# snowflake.net
KiCad netlist of a schematic drawn in EAGLE
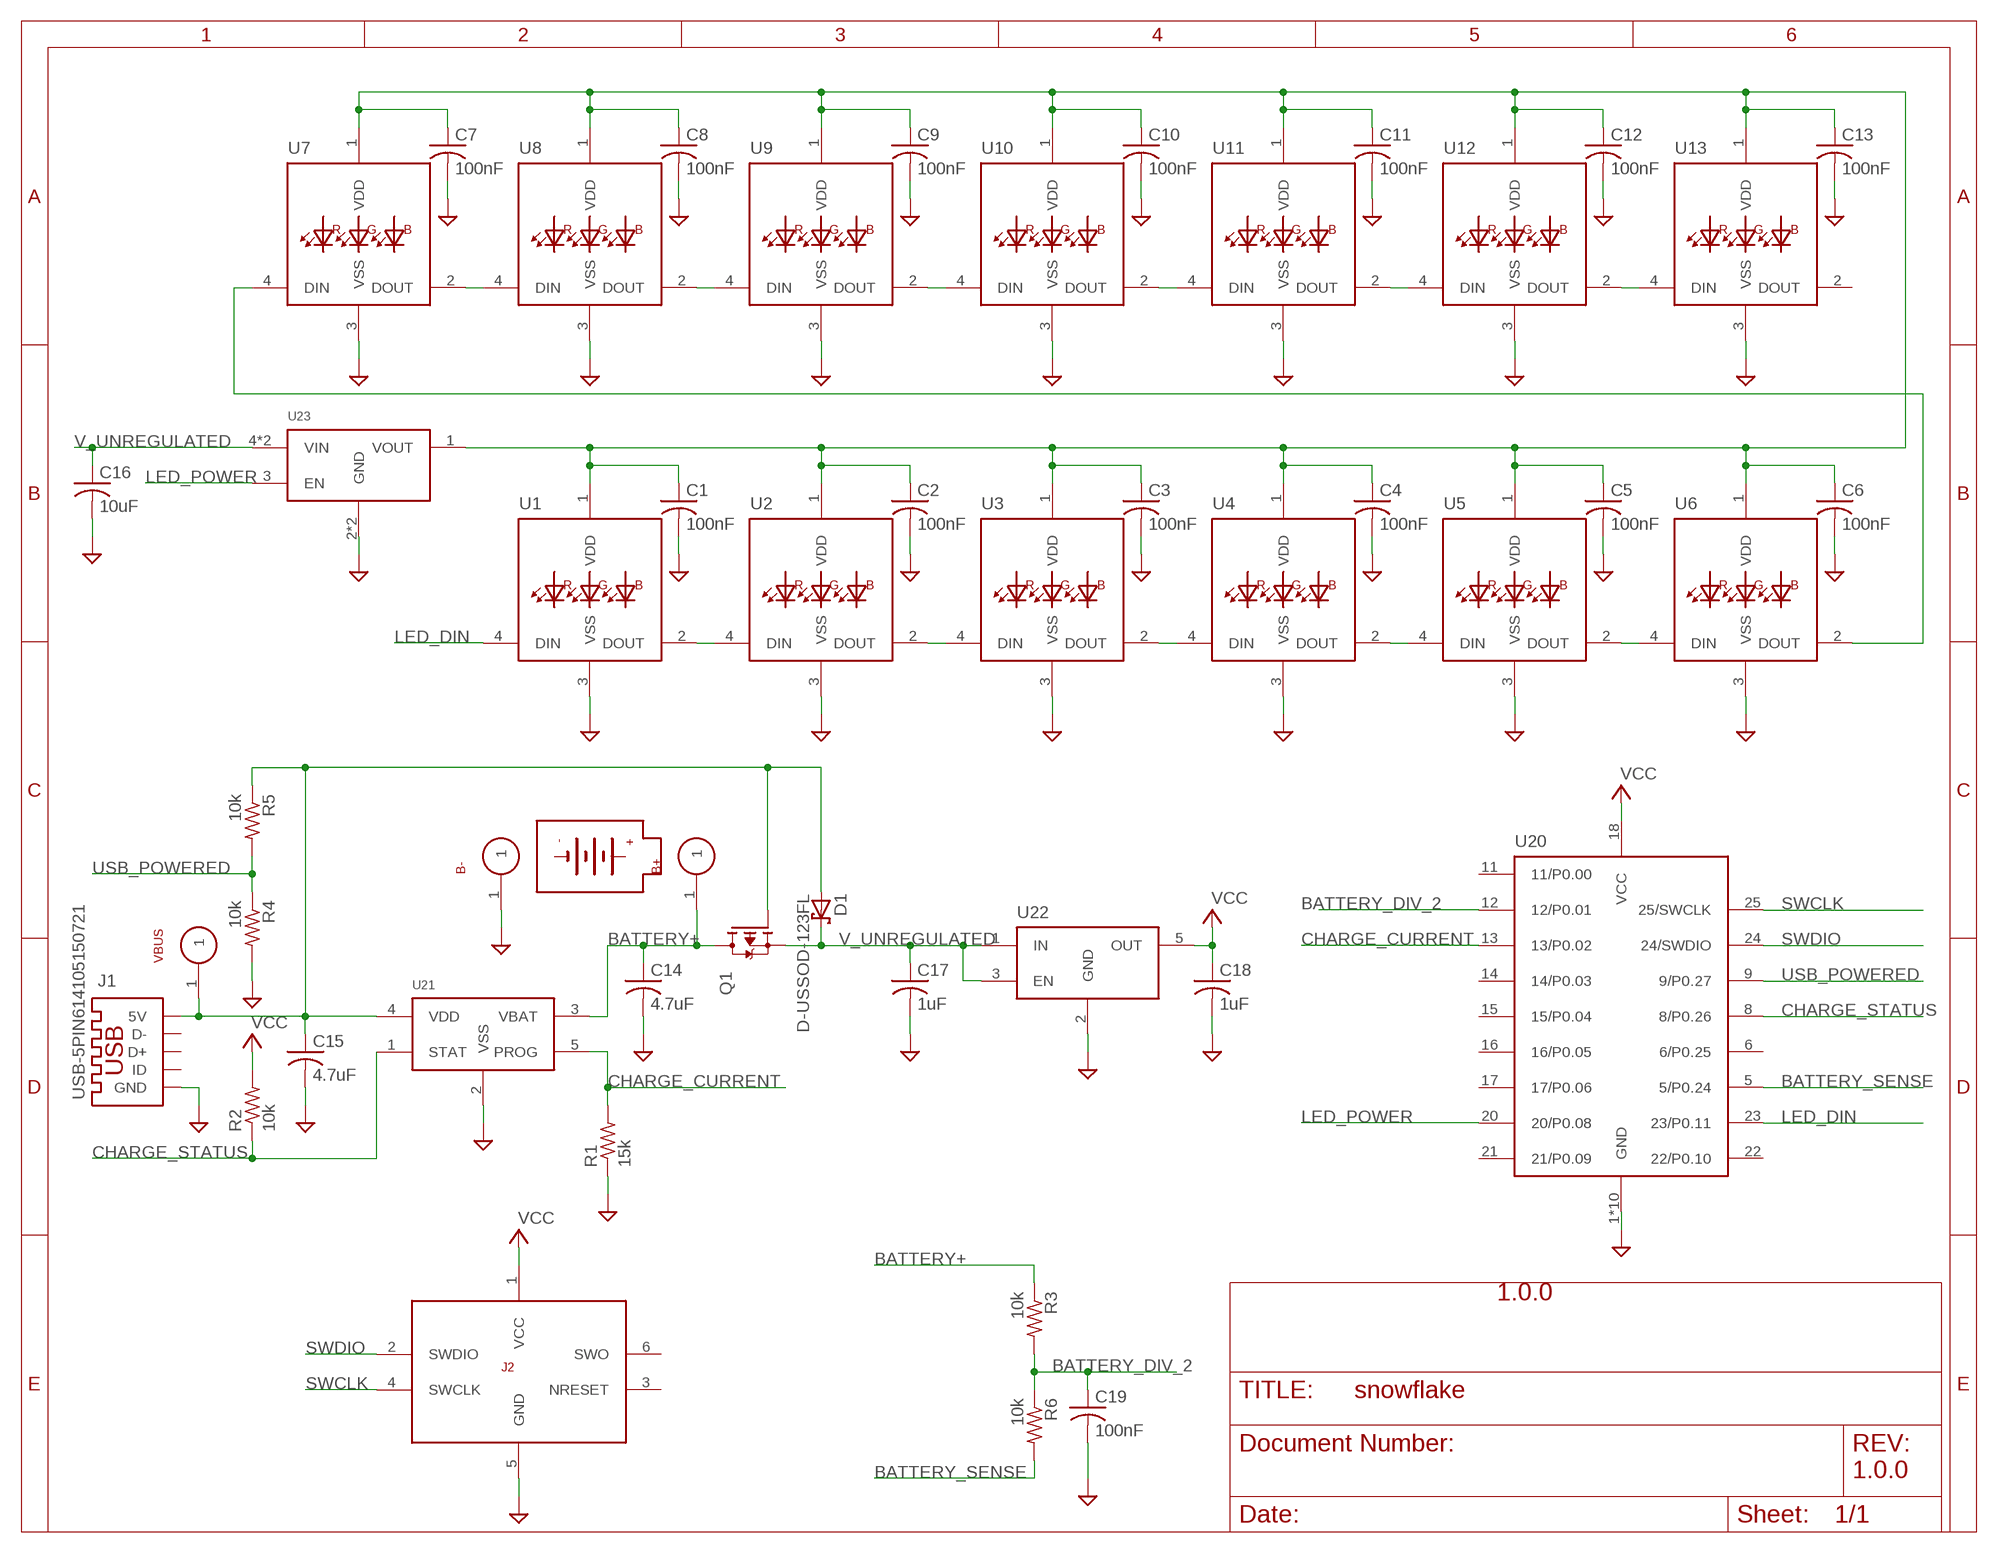
[diagram p0: schematic, sheet 1]

(export (version "E")
  (design (tool "Eeschema 10.0.6"))
  (components
    (comp (ref "B+")
      (value "TARGET-PINWP-28AWG")
      (footprint "eagle-import:WP-28AWG")
      (libsource (lib "eagle-import") (part "TARGET-PINWP-28AWG"))
    )
    (comp (ref "B-")
      (value "TARGET-PINWP-28AWG")
      (footprint "eagle-import:WP-28AWG")
      (libsource (lib "eagle-import") (part "TARGET-PINWP-28AWG"))
    )
    (comp (ref "B1")
      (value "BATTERY_SHAPEDTP401525")
      (footprint "eagle-import:DTP401525")
      (libsource (lib "eagle-import") (part "BATTERY_SHAPEDTP401525"))
    )
    (comp (ref "C1")
      (value "100nF")
      (footprint "eagle-import:C0805")
      (fields (field (name "MANUFACTURER") "Yageo"))
      (libsource (lib "eagle-import") (part "C-USC0805"))
    )
    (comp (ref "C2")
      (value "100nF")
      (footprint "eagle-import:C0805")
      (fields (field (name "MANUFACTURER") "Yageo"))
      (libsource (lib "eagle-import") (part "C-USC0805"))
    )
    (comp (ref "C3")
      (value "100nF")
      (footprint "eagle-import:C0805")
      (fields (field (name "MANUFACTURER") "Yageo"))
      (libsource (lib "eagle-import") (part "C-USC0805"))
    )
    (comp (ref "C4")
      (value "100nF")
      (footprint "eagle-import:C0805")
      (fields (field (name "MANUFACTURER") "Yageo"))
      (libsource (lib "eagle-import") (part "C-USC0805"))
    )
    (comp (ref "C5")
      (value "100nF")
      (footprint "eagle-import:C0805")
      (fields (field (name "MANUFACTURER") "Yageo"))
      (libsource (lib "eagle-import") (part "C-USC0805"))
    )
    (comp (ref "C6")
      (value "100nF")
      (footprint "eagle-import:C0805")
      (fields (field (name "MANUFACTURER") "Yageo"))
      (libsource (lib "eagle-import") (part "C-USC0805"))
    )
    (comp (ref "C7")
      (value "100nF")
      (footprint "eagle-import:C0805")
      (fields (field (name "MANUFACTURER") "Yageo"))
      (libsource (lib "eagle-import") (part "C-USC0805"))
    )
    (comp (ref "C8")
      (value "100nF")
      (footprint "eagle-import:C0805")
      (fields (field (name "MANUFACTURER") "Yageo"))
      (libsource (lib "eagle-import") (part "C-USC0805"))
    )
    (comp (ref "C9")
      (value "100nF")
      (footprint "eagle-import:C0805")
      (fields (field (name "MANUFACTURER") "Yageo"))
      (libsource (lib "eagle-import") (part "C-USC0805"))
    )
    (comp (ref "C10")
      (value "100nF")
      (footprint "eagle-import:C0805")
      (fields (field (name "MANUFACTURER") "Yageo"))
      (libsource (lib "eagle-import") (part "C-USC0805"))
    )
    (comp (ref "C11")
      (value "100nF")
      (footprint "eagle-import:C0805")
      (fields (field (name "MANUFACTURER") "Yageo"))
      (libsource (lib "eagle-import") (part "C-USC0805"))
    )
    (comp (ref "C12")
      (value "100nF")
      (footprint "eagle-import:C0805")
      (fields (field (name "MANUFACTURER") "Yageo"))
      (libsource (lib "eagle-import") (part "C-USC0805"))
    )
    (comp (ref "C13")
      (value "100nF")
      (footprint "eagle-import:C0805")
      (fields (field (name "MANUFACTURER") "Yageo"))
      (libsource (lib "eagle-import") (part "C-USC0805"))
    )
    (comp (ref "C14")
      (value "4.7uF")
      (footprint "eagle-import:C0805")
      (fields (field (name "MANUFACTURER") "Yaego"))
      (libsource (lib "eagle-import") (part "C-USC0805"))
    )
    (comp (ref "C15")
      (value "4.7uF")
      (footprint "eagle-import:C0805")
      (fields (field (name "MANUFACTURER") "Yaego"))
      (libsource (lib "eagle-import") (part "C-USC0805"))
    )
    (comp (ref "C16")
      (value "10uF")
      (footprint "eagle-import:C0805")
      (fields (field (name "MANUFACTURER") "YAEGO"))
      (libsource (lib "eagle-import") (part "C-USC0805"))
    )
    (comp (ref "C17")
      (value "1uF")
      (footprint "eagle-import:C0805")
      (fields (field (name "MANUFACTURER") "YAGEO"))
      (libsource (lib "eagle-import") (part "C-USC0805"))
    )
    (comp (ref "C18")
      (value "1uF")
      (footprint "eagle-import:C0805")
      (fields (field (name "MANUFACTURER") "Yageo"))
      (libsource (lib "eagle-import") (part "C-USC0805"))
    )
    (comp (ref "C19")
      (value "100nF")
      (footprint "eagle-import:C0805")
      (fields (field (name "MANUFACTURER") "Yaego"))
      (libsource (lib "eagle-import") (part "C-USC0805"))
    )
    (comp (ref "D1")
      (value "D-USSOD-123FL")
      (footprint "eagle-import:SOD-123FL")
      (fields (field (name "MANUFACTURER") "ON Semiconductor"))
      (libsource (lib "eagle-import") (part "D-USSOD-123FL"))
    )
    (comp (ref "J1")
      (value "USB-5PIN614105150721")
      (footprint "eagle-import:614105150721")
      (fields (field (name "MANUFACTURER") "Wurth Electronics Inc"))
      (libsource (lib "eagle-import") (part "USB-5PIN614105150721"))
    )
    (comp (ref "J2")
      (value "TC2030-SWD")
      (footprint "eagle-import:TC2030-MCP-NL")
      (libsource (lib "eagle-import") (part "TC2030-SWD"))
    )
    (comp (ref "Q1")
      (value "FET-PSOT-23-3")
      (footprint "eagle-import:SOT-23-3")
      (fields (field (name "MANUFACTURER") "Toshiba Semiconductor and Storage"))
      (libsource (lib "eagle-import") (part "FET-PSOT-23-3"))
    )
    (comp (ref "R1")
      (value "15k")
      (footprint "eagle-import:R0805")
      (fields (field (name "MANUFACTURER") "Yageo"))
      (libsource (lib "eagle-import") (part "R-USR0805"))
    )
    (comp (ref "R2")
      (value "10k")
      (footprint "eagle-import:R0805")
      (fields (field (name "MANUFACTURER") "Yageo"))
      (libsource (lib "eagle-import") (part "R-USR0805"))
    )
    (comp (ref "R3")
      (value "10k")
      (footprint "eagle-import:R0805")
      (fields (field (name "MANUFACTURER") "Yageo"))
      (libsource (lib "eagle-import") (part "R-USR0805"))
    )
    (comp (ref "R4")
      (value "10k")
      (footprint "eagle-import:R0805")
      (fields (field (name "MANUFACTURER") "Yageo"))
      (libsource (lib "eagle-import") (part "R-USR0805"))
    )
    (comp (ref "R5")
      (value "10k")
      (footprint "eagle-import:R0805")
      (fields (field (name "MANUFACTURER") "Yageo"))
      (libsource (lib "eagle-import") (part "R-USR0805"))
    )
    (comp (ref "R6")
      (value "10k")
      (footprint "eagle-import:R0805")
      (fields (field (name "MANUFACTURER") "Yageo"))
      (libsource (lib "eagle-import") (part "R-USR0805"))
    )
    (comp (ref "U1")
      (value "WS2812B")
      (footprint "eagle-import:WS2812B")
      (fields (field (name "MANUFACTURER") "worldsemi"))
      (libsource (lib "eagle-import") (part "WS2812B"))
    )
    (comp (ref "U2")
      (value "WS2812B")
      (footprint "eagle-import:WS2812B")
      (fields (field (name "MANUFACTURER") "worldsemi"))
      (libsource (lib "eagle-import") (part "WS2812B"))
    )
    (comp (ref "U3")
      (value "WS2812B")
      (footprint "eagle-import:WS2812B")
      (fields (field (name "MANUFACTURER") "worldsemi"))
      (libsource (lib "eagle-import") (part "WS2812B"))
    )
    (comp (ref "U4")
      (value "WS2812B")
      (footprint "eagle-import:WS2812B")
      (fields (field (name "MANUFACTURER") "worldsemi"))
      (libsource (lib "eagle-import") (part "WS2812B"))
    )
    (comp (ref "U5")
      (value "WS2812B")
      (footprint "eagle-import:WS2812B")
      (fields (field (name "MANUFACTURER") "worldsemi"))
      (libsource (lib "eagle-import") (part "WS2812B"))
    )
    (comp (ref "U6")
      (value "WS2812B")
      (footprint "eagle-import:WS2812B")
      (fields (field (name "MANUFACTURER") "worldsemi"))
      (libsource (lib "eagle-import") (part "WS2812B"))
    )
    (comp (ref "U7")
      (value "WS2812B")
      (footprint "eagle-import:WS2812B")
      (fields (field (name "MANUFACTURER") "worldsemi"))
      (libsource (lib "eagle-import") (part "WS2812B"))
    )
    (comp (ref "U8")
      (value "WS2812B")
      (footprint "eagle-import:WS2812B")
      (fields (field (name "MANUFACTURER") "worldsemi"))
      (libsource (lib "eagle-import") (part "WS2812B"))
    )
    (comp (ref "U9")
      (value "WS2812B")
      (footprint "eagle-import:WS2812B")
      (fields (field (name "MANUFACTURER") "worldsemi"))
      (libsource (lib "eagle-import") (part "WS2812B"))
    )
    (comp (ref "U10")
      (value "WS2812B")
      (footprint "eagle-import:WS2812B")
      (fields (field (name "MANUFACTURER") "worldsemi"))
      (libsource (lib "eagle-import") (part "WS2812B"))
    )
    (comp (ref "U11")
      (value "WS2812B")
      (footprint "eagle-import:WS2812B")
      (fields (field (name "MANUFACTURER") "worldsemi"))
      (libsource (lib "eagle-import") (part "WS2812B"))
    )
    (comp (ref "U12")
      (value "WS2812B")
      (footprint "eagle-import:WS2812B")
      (fields (field (name "MANUFACTURER") "worldsemi"))
      (libsource (lib "eagle-import") (part "WS2812B"))
    )
    (comp (ref "U13")
      (value "WS2812B")
      (footprint "eagle-import:WS2812B")
      (fields (field (name "MANUFACTURER") "worldsemi"))
      (libsource (lib "eagle-import") (part "WS2812B"))
    )
    (comp (ref "U20")
      (value "BMD-200")
      (footprint "eagle-import:BMD-200")
      (fields (field (name "MANUFACTURER") "Rigado LLC"))
      (libsource (lib "eagle-import") (part "BMD-200"))
    )
    (comp (ref "U21")
      (value "MCP73832SOT-23-5")
      (footprint "eagle-import:SOT-23-5")
      (fields (field (name "MANUFACTURER") "Microchip Technology"))
      (libsource (lib "eagle-import") (part "MCP73832SOT-23-5"))
    )
    (comp (ref "U22")
      (value "ADP160")
      (footprint "eagle-import:TSOT-5")
      (fields (field (name "MANUFACTURER") "Analog Devices Inc."))
      (libsource (lib "eagle-import") (part "ADP160"))
    )
    (comp (ref "U23")
      (value "TPS22929D")
      (footprint "eagle-import:SOT-23-6")
      (fields (field (name "MANUFACTURER") "Toshiba Semiconductor and Storage"))
      (libsource (lib "eagle-import") (part "TPS22929D"))
    )
    (comp (ref "VBUS")
      (value "TARGET-PIN")
      (footprint "eagle-import:TARGET-PIN-1MM")
      (libsource (lib "eagle-import") (part "TARGET-PIN"))
    )
  )
  (nets
    (net (code "1") (name "/BATTERY+") (class "Default")
      (node (ref "B+") (pin "1") (pinfunction "1_1") (pintype "bidirectional"))
      (node (ref "C14") (pin "1") (pinfunction "1_1") (pintype "passive"))
      (node (ref "Q1") (pin "3") (pinfunction "D_3") (pintype "passive"))
      (node (ref "R3") (pin "1") (pinfunction "1_1") (pintype "passive"))
      (node (ref "U21") (pin "3") (pinfunction "VBAT_3") (pintype "bidirectional"))
    )
    (net (code "2") (name "/BATTERY_DIV_2") (class "Default")
      (node (ref "C19") (pin "1") (pinfunction "1_1") (pintype "passive"))
      (node (ref "R3") (pin "2") (pinfunction "2_2") (pintype "passive"))
      (node (ref "R6") (pin "1") (pinfunction "1_1") (pintype "passive"))
      (node (ref "U20") (pin "12") (pinfunction "12/P0.01_12") (pintype "bidirectional"))
    )
    (net (code "3") (name "/BATTERY_SENSE") (class "Default")
      (node (ref "R6") (pin "2") (pinfunction "2_2") (pintype "passive"))
      (node (ref "U20") (pin "5") (pinfunction "5/P0.24_5") (pintype "bidirectional"))
    )
    (net (code "4") (name "/CHARGE_CURRENT") (class "Default")
      (node (ref "R1") (pin "2") (pinfunction "2_2") (pintype "passive"))
      (node (ref "U20") (pin "13") (pinfunction "13/P0.02_13") (pintype "bidirectional"))
      (node (ref "U21") (pin "5") (pinfunction "PROG_5") (pintype "bidirectional"))
    )
    (net (code "5") (name "/CHARGE_STATUS") (class "Default")
      (node (ref "R2") (pin "1") (pinfunction "1_1") (pintype "passive"))
      (node (ref "U20") (pin "8") (pinfunction "8/P0.26_8") (pintype "bidirectional"))
      (node (ref "U21") (pin "1") (pinfunction "STAT_1") (pintype "bidirectional"))
    )
    (net (code "6") (name "/LED_DIN") (class "Default")
      (node (ref "U1") (pin "4") (pinfunction "DIN_4") (pintype "bidirectional"))
      (node (ref "U20") (pin "23") (pinfunction "23/P0.11_23") (pintype "bidirectional"))
    )
    (net (code "7") (name "/LED_POWER") (class "Default")
      (node (ref "U20") (pin "20") (pinfunction "20/P0.08_20") (pintype "bidirectional"))
      (node (ref "U23") (pin "3") (pinfunction "EN_3") (pintype "bidirectional"))
    )
    (net (code "8") (name "/SWCLK") (class "Default")
      (node (ref "J2") (pin "4") (pinfunction "SWCLK_4") (pintype "bidirectional"))
      (node (ref "U20") (pin "25") (pinfunction "25/SWCLK_25") (pintype "bidirectional"))
    )
    (net (code "9") (name "/SWDIO") (class "Default")
      (node (ref "J2") (pin "2") (pinfunction "SWDIO_2") (pintype "bidirectional"))
      (node (ref "U20") (pin "24") (pinfunction "24/SWDIO_24") (pintype "bidirectional"))
    )
    (net (code "10") (name "/USB_POWERED") (class "Default")
      (node (ref "R4") (pin "1") (pinfunction "1_1") (pintype "passive"))
      (node (ref "R5") (pin "2") (pinfunction "2_2") (pintype "passive"))
      (node (ref "U20") (pin "9") (pinfunction "9/P0.27_9") (pintype "bidirectional"))
    )
    (net (code "11") (name "/V_UNREGULATED") (class "Default")
      (node (ref "C16") (pin "1") (pinfunction "1_1") (pintype "passive"))
      (node (ref "C17") (pin "1") (pinfunction "1_1") (pintype "passive"))
      (node (ref "D1") (pin "C") (pinfunction "C_C") (pintype "passive"))
      (node (ref "Q1") (pin "2") (pinfunction "S_2") (pintype "passive"))
      (node (ref "U22") (pin "1") (pinfunction "IN_1") (pintype "bidirectional"))
      (node (ref "U22") (pin "3") (pinfunction "EN_3") (pintype "bidirectional"))
      (node (ref "U23") (pin "4") (pinfunction "VIN_4") (pintype "bidirectional"))
      (node (ref "U23") (pin "6") (pinfunction "VIN_6") (pintype "bidirectional"))
    )
    (net (code "12") (name "GND") (class "Default")
      (node (ref "B-") (pin "1") (pinfunction "1_1") (pintype "bidirectional"))
      (node (ref "C1") (pin "2") (pinfunction "2_2") (pintype "passive"))
      (node (ref "C10") (pin "2") (pinfunction "2_2") (pintype "passive"))
      (node (ref "C11") (pin "2") (pinfunction "2_2") (pintype "passive"))
      (node (ref "C12") (pin "2") (pinfunction "2_2") (pintype "passive"))
      (node (ref "C13") (pin "2") (pinfunction "2_2") (pintype "passive"))
      (node (ref "C14") (pin "2") (pinfunction "2_2") (pintype "passive"))
      (node (ref "C15") (pin "2") (pinfunction "2_2") (pintype "passive"))
      (node (ref "C16") (pin "2") (pinfunction "2_2") (pintype "passive"))
      (node (ref "C17") (pin "2") (pinfunction "2_2") (pintype "passive"))
      (node (ref "C18") (pin "2") (pinfunction "2_2") (pintype "passive"))
      (node (ref "C19") (pin "2") (pinfunction "2_2") (pintype "passive"))
      (node (ref "C2") (pin "2") (pinfunction "2_2") (pintype "passive"))
      (node (ref "C3") (pin "2") (pinfunction "2_2") (pintype "passive"))
      (node (ref "C4") (pin "2") (pinfunction "2_2") (pintype "passive"))
      (node (ref "C5") (pin "2") (pinfunction "2_2") (pintype "passive"))
      (node (ref "C6") (pin "2") (pinfunction "2_2") (pintype "passive"))
      (node (ref "C7") (pin "2") (pinfunction "2_2") (pintype "passive"))
      (node (ref "C8") (pin "2") (pinfunction "2_2") (pintype "passive"))
      (node (ref "C9") (pin "2") (pinfunction "2_2") (pintype "passive"))
      (node (ref "J1") (pin "5") (pinfunction "GND_5") (pintype "bidirectional"))
      (node (ref "J2") (pin "5") (pinfunction "GND_5") (pintype "bidirectional"))
      (node (ref "R1") (pin "1") (pinfunction "1_1") (pintype "passive"))
      (node (ref "R4") (pin "2") (pinfunction "2_2") (pintype "passive"))
      (node (ref "U1") (pin "3") (pinfunction "VSS_3") (pintype "bidirectional"))
      (node (ref "U10") (pin "3") (pinfunction "VSS_3") (pintype "bidirectional"))
      (node (ref "U11") (pin "3") (pinfunction "VSS_3") (pintype "bidirectional"))
      (node (ref "U12") (pin "3") (pinfunction "VSS_3") (pintype "bidirectional"))
      (node (ref "U13") (pin "3") (pinfunction "VSS_3") (pintype "bidirectional"))
      (node (ref "U2") (pin "3") (pinfunction "VSS_3") (pintype "bidirectional"))
      (node (ref "U20") (pin "1") (pinfunction "GND_1") (pintype "bidirectional"))
      (node (ref "U20") (pin "10") (pinfunction "GND_10") (pintype "bidirectional"))
      (node (ref "U20") (pin "19") (pinfunction "GND_19") (pintype "bidirectional"))
      (node (ref "U20") (pin "2") (pinfunction "GND_2") (pintype "bidirectional"))
      (node (ref "U20") (pin "26") (pinfunction "GND_26") (pintype "bidirectional"))
      (node (ref "U20") (pin "27") (pinfunction "GND_27") (pintype "bidirectional"))
      (node (ref "U20") (pin "28") (pinfunction "GND_28") (pintype "bidirectional"))
      (node (ref "U20") (pin "3") (pinfunction "GND_3") (pintype "bidirectional"))
      (node (ref "U20") (pin "4") (pinfunction "GND_4") (pintype "bidirectional"))
      (node (ref "U20") (pin "7") (pinfunction "GND_7") (pintype "bidirectional"))
      (node (ref "U21") (pin "2") (pinfunction "VSS_2") (pintype "bidirectional"))
      (node (ref "U22") (pin "2") (pinfunction "GND_2") (pintype "bidirectional"))
      (node (ref "U23") (pin "2") (pinfunction "GND_2") (pintype "bidirectional"))
      (node (ref "U23") (pin "5") (pinfunction "GND_5") (pintype "bidirectional"))
      (node (ref "U3") (pin "3") (pinfunction "VSS_3") (pintype "bidirectional"))
      (node (ref "U4") (pin "3") (pinfunction "VSS_3") (pintype "bidirectional"))
      (node (ref "U5") (pin "3") (pinfunction "VSS_3") (pintype "bidirectional"))
      (node (ref "U6") (pin "3") (pinfunction "VSS_3") (pintype "bidirectional"))
      (node (ref "U7") (pin "3") (pinfunction "VSS_3") (pintype "bidirectional"))
      (node (ref "U8") (pin "3") (pinfunction "VSS_3") (pintype "bidirectional"))
      (node (ref "U9") (pin "3") (pinfunction "VSS_3") (pintype "bidirectional"))
    )
    (net (code "13") (name "Net-(J1-5V)") (class "Default")
      (node (ref "C15") (pin "1") (pinfunction "1_1") (pintype "passive"))
      (node (ref "D1") (pin "A") (pinfunction "A_A") (pintype "passive"))
      (node (ref "J1") (pin "1") (pinfunction "5V_1") (pintype "bidirectional"))
      (node (ref "Q1") (pin "1") (pinfunction "G_1") (pintype "passive"))
      (node (ref "R5") (pin "1") (pinfunction "1_1") (pintype "passive"))
      (node (ref "U21") (pin "4") (pinfunction "VDD_4") (pintype "bidirectional"))
      (node (ref "VBUS") (pin "1") (pinfunction "1_1") (pintype "bidirectional"))
    )
    (net (code "14") (name "Net-(U1-DOUT)") (class "Default")
      (node (ref "U1") (pin "2") (pinfunction "DOUT_2") (pintype "bidirectional"))
      (node (ref "U2") (pin "4") (pinfunction "DIN_4") (pintype "bidirectional"))
    )
    (net (code "15") (name "Net-(U1-VDD)") (class "Default")
      (node (ref "C1") (pin "1") (pinfunction "1_1") (pintype "passive"))
      (node (ref "C10") (pin "1") (pinfunction "1_1") (pintype "passive"))
      (node (ref "C11") (pin "1") (pinfunction "1_1") (pintype "passive"))
      (node (ref "C12") (pin "1") (pinfunction "1_1") (pintype "passive"))
      (node (ref "C13") (pin "1") (pinfunction "1_1") (pintype "passive"))
      (node (ref "C2") (pin "1") (pinfunction "1_1") (pintype "passive"))
      (node (ref "C3") (pin "1") (pinfunction "1_1") (pintype "passive"))
      (node (ref "C4") (pin "1") (pinfunction "1_1") (pintype "passive"))
      (node (ref "C5") (pin "1") (pinfunction "1_1") (pintype "passive"))
      (node (ref "C6") (pin "1") (pinfunction "1_1") (pintype "passive"))
      (node (ref "C7") (pin "1") (pinfunction "1_1") (pintype "passive"))
      (node (ref "C8") (pin "1") (pinfunction "1_1") (pintype "passive"))
      (node (ref "C9") (pin "1") (pinfunction "1_1") (pintype "passive"))
      (node (ref "U1") (pin "1") (pinfunction "VDD_1") (pintype "bidirectional"))
      (node (ref "U10") (pin "1") (pinfunction "VDD_1") (pintype "bidirectional"))
      (node (ref "U11") (pin "1") (pinfunction "VDD_1") (pintype "bidirectional"))
      (node (ref "U12") (pin "1") (pinfunction "VDD_1") (pintype "bidirectional"))
      (node (ref "U13") (pin "1") (pinfunction "VDD_1") (pintype "bidirectional"))
      (node (ref "U2") (pin "1") (pinfunction "VDD_1") (pintype "bidirectional"))
      (node (ref "U23") (pin "1") (pinfunction "VOUT_1") (pintype "bidirectional"))
      (node (ref "U3") (pin "1") (pinfunction "VDD_1") (pintype "bidirectional"))
      (node (ref "U4") (pin "1") (pinfunction "VDD_1") (pintype "bidirectional"))
      (node (ref "U5") (pin "1") (pinfunction "VDD_1") (pintype "bidirectional"))
      (node (ref "U6") (pin "1") (pinfunction "VDD_1") (pintype "bidirectional"))
      (node (ref "U7") (pin "1") (pinfunction "VDD_1") (pintype "bidirectional"))
      (node (ref "U8") (pin "1") (pinfunction "VDD_1") (pintype "bidirectional"))
      (node (ref "U9") (pin "1") (pinfunction "VDD_1") (pintype "bidirectional"))
    )
    (net (code "16") (name "Net-(U2-DOUT)") (class "Default")
      (node (ref "U2") (pin "2") (pinfunction "DOUT_2") (pintype "bidirectional"))
      (node (ref "U3") (pin "4") (pinfunction "DIN_4") (pintype "bidirectional"))
    )
    (net (code "17") (name "Net-(U3-DOUT)") (class "Default")
      (node (ref "U3") (pin "2") (pinfunction "DOUT_2") (pintype "bidirectional"))
      (node (ref "U4") (pin "4") (pinfunction "DIN_4") (pintype "bidirectional"))
    )
    (net (code "18") (name "Net-(U4-DOUT)") (class "Default")
      (node (ref "U4") (pin "2") (pinfunction "DOUT_2") (pintype "bidirectional"))
      (node (ref "U5") (pin "4") (pinfunction "DIN_4") (pintype "bidirectional"))
    )
    (net (code "19") (name "Net-(U5-DOUT)") (class "Default")
      (node (ref "U5") (pin "2") (pinfunction "DOUT_2") (pintype "bidirectional"))
      (node (ref "U6") (pin "4") (pinfunction "DIN_4") (pintype "bidirectional"))
    )
    (net (code "20") (name "Net-(U6-DOUT)") (class "Default")
      (node (ref "U6") (pin "2") (pinfunction "DOUT_2") (pintype "bidirectional"))
      (node (ref "U7") (pin "4") (pinfunction "DIN_4") (pintype "bidirectional"))
    )
    (net (code "21") (name "Net-(U7-DOUT)") (class "Default")
      (node (ref "U7") (pin "2") (pinfunction "DOUT_2") (pintype "bidirectional"))
      (node (ref "U8") (pin "4") (pinfunction "DIN_4") (pintype "bidirectional"))
    )
    (net (code "22") (name "Net-(U8-DOUT)") (class "Default")
      (node (ref "U8") (pin "2") (pinfunction "DOUT_2") (pintype "bidirectional"))
      (node (ref "U9") (pin "4") (pinfunction "DIN_4") (pintype "bidirectional"))
    )
    (net (code "23") (name "Net-(U10-DIN)") (class "Default")
      (node (ref "U10") (pin "4") (pinfunction "DIN_4") (pintype "bidirectional"))
      (node (ref "U9") (pin "2") (pinfunction "DOUT_2") (pintype "bidirectional"))
    )
    (net (code "24") (name "Net-(U10-DOUT)") (class "Default")
      (node (ref "U10") (pin "2") (pinfunction "DOUT_2") (pintype "bidirectional"))
      (node (ref "U11") (pin "4") (pinfunction "DIN_4") (pintype "bidirectional"))
    )
    (net (code "25") (name "Net-(U11-DOUT)") (class "Default")
      (node (ref "U11") (pin "2") (pinfunction "DOUT_2") (pintype "bidirectional"))
      (node (ref "U12") (pin "4") (pinfunction "DIN_4") (pintype "bidirectional"))
    )
    (net (code "26") (name "Net-(U12-DOUT)") (class "Default")
      (node (ref "U12") (pin "2") (pinfunction "DOUT_2") (pintype "bidirectional"))
      (node (ref "U13") (pin "4") (pinfunction "DIN_4") (pintype "bidirectional"))
    )
    (net (code "27") (name "VCC") (class "Default")
      (node (ref "C18") (pin "1") (pinfunction "1_1") (pintype "passive"))
      (node (ref "J2") (pin "1") (pinfunction "VCC_1") (pintype "bidirectional"))
      (node (ref "R2") (pin "2") (pinfunction "2_2") (pintype "passive"))
      (node (ref "U20") (pin "18") (pinfunction "VCC_18") (pintype "bidirectional"))
      (node (ref "U22") (pin "5") (pinfunction "OUT_5") (pintype "bidirectional"))
    )
    (net (code "28") (name "unconnected-(J1-D+-Pad3)") (class "Default")
      (node (ref "J1") (pin "3") (pinfunction "D+_3") (pintype "bidirectional"))
    )
    (net (code "29") (name "unconnected-(J1-D--Pad2)") (class "Default")
      (node (ref "J1") (pin "2") (pinfunction "D-_2") (pintype "bidirectional"))
    )
    (net (code "30") (name "unconnected-(J1-ID-Pad4)") (class "Default")
      (node (ref "J1") (pin "4") (pinfunction "ID_4") (pintype "bidirectional"))
    )
    (net (code "31") (name "unconnected-(J2-NRESET-Pad3)") (class "Default")
      (node (ref "J2") (pin "3") (pinfunction "NRESET_3") (pintype "bidirectional"))
    )
    (net (code "32") (name "unconnected-(J2-SWO-Pad6)") (class "Default")
      (node (ref "J2") (pin "6") (pinfunction "SWO_6") (pintype "bidirectional"))
    )
    (net (code "33") (name "unconnected-(U13-DOUT-Pad2)") (class "Default")
      (node (ref "U13") (pin "2") (pinfunction "DOUT_2") (pintype "bidirectional"))
    )
    (net (code "34") (name "unconnected-(U20-6{slash}P0.25-Pad6)") (class "Default")
      (node (ref "U20") (pin "6") (pinfunction "6/P0.25_6") (pintype "bidirectional"))
    )
    (net (code "35") (name "unconnected-(U20-11{slash}P0.00-Pad11)") (class "Default")
      (node (ref "U20") (pin "11") (pinfunction "11/P0.00_11") (pintype "bidirectional"))
    )
    (net (code "36") (name "unconnected-(U20-14{slash}P0.03-Pad14)") (class "Default")
      (node (ref "U20") (pin "14") (pinfunction "14/P0.03_14") (pintype "bidirectional"))
    )
    (net (code "37") (name "unconnected-(U20-15{slash}P0.04-Pad15)") (class "Default")
      (node (ref "U20") (pin "15") (pinfunction "15/P0.04_15") (pintype "bidirectional"))
    )
    (net (code "38") (name "unconnected-(U20-16{slash}P0.05-Pad16)") (class "Default")
      (node (ref "U20") (pin "16") (pinfunction "16/P0.05_16") (pintype "bidirectional"))
    )
    (net (code "39") (name "unconnected-(U20-17{slash}P0.06-Pad17)") (class "Default")
      (node (ref "U20") (pin "17") (pinfunction "17/P0.06_17") (pintype "bidirectional"))
    )
    (net (code "40") (name "unconnected-(U20-21{slash}P0.09-Pad21)") (class "Default")
      (node (ref "U20") (pin "21") (pinfunction "21/P0.09_21") (pintype "bidirectional"))
    )
    (net (code "41") (name "unconnected-(U20-22{slash}P0.10-Pad22)") (class "Default")
      (node (ref "U20") (pin "22") (pinfunction "22/P0.10_22") (pintype "bidirectional"))
    )
  )
)
